# PicLEDThermometer.net
KiCad netlist of a schematic drawn in EAGLE
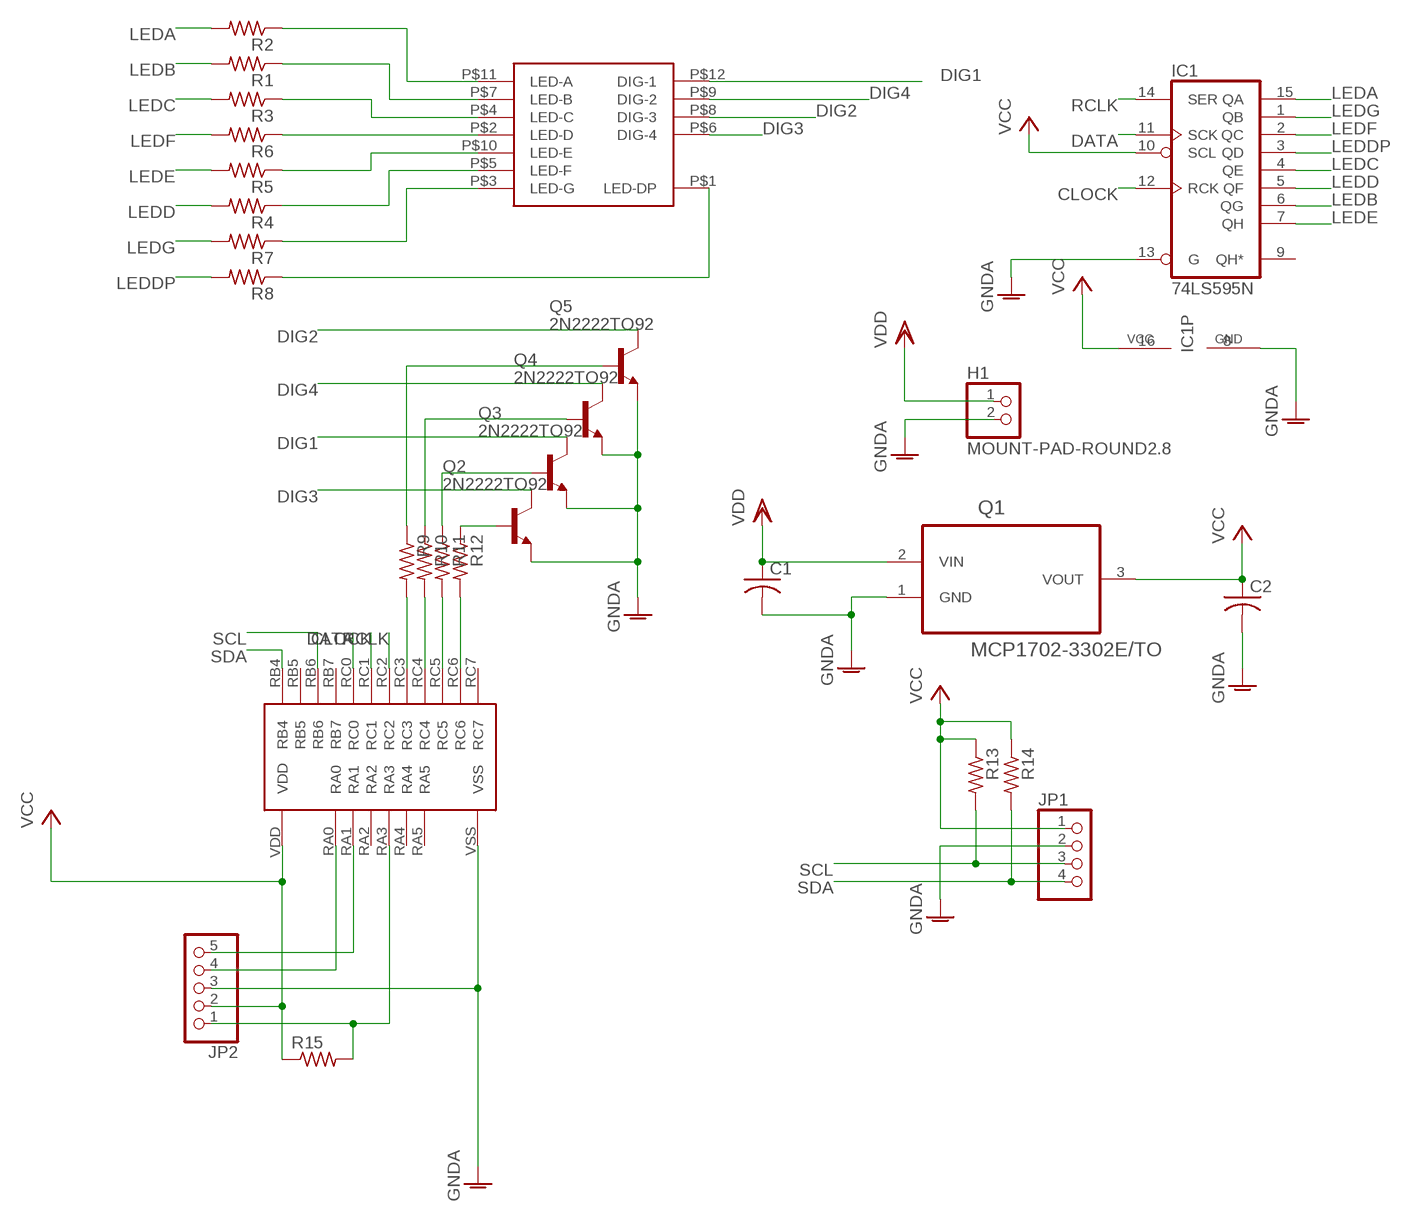
[diagram p0: schematic, sheet 1]

(export (version "E")
  (design (tool "Eeschema 10.0.6"))
  (components
    (comp (ref "C1")
      (value "C-US025-030X050")
      (footprint "eagle-import:C025-030X050")
      (libsource (lib "eagle-import") (part "C-US025-030X050"))
    )
    (comp (ref "C2")
      (value "C-US025-030X050")
      (footprint "eagle-import:C025-030X050")
      (libsource (lib "eagle-import") (part "C-US025-030X050"))
    )
    (comp (ref "H1")
      (value "MOUNT-PAD-ROUND2.8")
      (footprint "eagle-import:1X02")
      (libsource (lib "eagle-import") (part "PINHD-1X2"))
    )
    (comp (ref "IC1")
      (value "74LS595N")
      (footprint "eagle-import:DIL16")
      (libsource (lib "eagle-import") (part "74595NLS"))
    )
    (comp (ref "JP1")
      (value "PINHD-1X4")
      (footprint "eagle-import:1X04")
      (libsource (lib "eagle-import") (part "PINHD-1X4"))
    )
    (comp (ref "JP2")
      (value "PINHD-1X5")
      (footprint "eagle-import:1X05")
      (libsource (lib "eagle-import") (part "PINHD-1X5"))
    )
    (comp (ref "Q1")
      (value "MCP1702-3302E/TO")
      (footprint "eagle-import:TO127P254X533-3")
      (libsource (lib "eagle-import") (part "MCP1702-3302E/TO"))
    )
    (comp (ref "Q2")
      (value "2N2222TO92")
      (footprint "eagle-import:TO92-LINE")
      (libsource (lib "eagle-import") (part "2N2222TO92"))
    )
    (comp (ref "Q3")
      (value "2N2222TO92")
      (footprint "eagle-import:TO92-LINE")
      (libsource (lib "eagle-import") (part "2N2222TO92"))
    )
    (comp (ref "Q4")
      (value "2N2222TO92")
      (footprint "eagle-import:TO92-LINE")
      (libsource (lib "eagle-import") (part "2N2222TO92"))
    )
    (comp (ref "Q5")
      (value "2N2222TO92")
      (footprint "eagle-import:TO92-LINE")
      (libsource (lib "eagle-import") (part "2N2222TO92"))
    )
    (comp (ref "R1")
      (value "R-US_0207/10")
      (footprint "eagle-import:0207_10")
      (libsource (lib "eagle-import") (part "R-US_0207/10"))
    )
    (comp (ref "R2")
      (value "R-US_0207/10")
      (footprint "eagle-import:0207_10")
      (libsource (lib "eagle-import") (part "R-US_0207/10"))
    )
    (comp (ref "R3")
      (value "R-US_0207/10")
      (footprint "eagle-import:0207_10")
      (libsource (lib "eagle-import") (part "R-US_0207/10"))
    )
    (comp (ref "R4")
      (value "R-US_0207/10")
      (footprint "eagle-import:0207_10")
      (libsource (lib "eagle-import") (part "R-US_0207/10"))
    )
    (comp (ref "R5")
      (value "R-US_0207/10")
      (footprint "eagle-import:0207_10")
      (libsource (lib "eagle-import") (part "R-US_0207/10"))
    )
    (comp (ref "R6")
      (value "R-US_0207/10")
      (footprint "eagle-import:0207_10")
      (libsource (lib "eagle-import") (part "R-US_0207/10"))
    )
    (comp (ref "R7")
      (value "R-US_0207/10")
      (footprint "eagle-import:0207_10")
      (libsource (lib "eagle-import") (part "R-US_0207/10"))
    )
    (comp (ref "R8")
      (value "R-US_0207/10")
      (footprint "eagle-import:0207_10")
      (libsource (lib "eagle-import") (part "R-US_0207/10"))
    )
    (comp (ref "R9")
      (value "R-US_0207/10")
      (footprint "eagle-import:0207_10")
      (libsource (lib "eagle-import") (part "R-US_0207/10"))
    )
    (comp (ref "R10")
      (value "R-US_0207/10")
      (footprint "eagle-import:0207_10")
      (libsource (lib "eagle-import") (part "R-US_0207/10"))
    )
    (comp (ref "R11")
      (value "R-US_0207/10")
      (footprint "eagle-import:0207_10")
      (libsource (lib "eagle-import") (part "R-US_0207/10"))
    )
    (comp (ref "R12")
      (value "R-US_0207/10")
      (footprint "eagle-import:0207_10")
      (libsource (lib "eagle-import") (part "R-US_0207/10"))
    )
    (comp (ref "R13")
      (value "R-US_0207/10")
      (footprint "eagle-import:0207_10")
      (libsource (lib "eagle-import") (part "R-US_0207/10"))
    )
    (comp (ref "R14")
      (value "R-US_0207/10")
      (footprint "eagle-import:0207_10")
      (libsource (lib "eagle-import") (part "R-US_0207/10"))
    )
    (comp (ref "R15")
      (value "R-US_0207/10")
      (footprint "eagle-import:0207_10")
      (libsource (lib "eagle-import") (part "R-US_0207/10"))
    )
    (comp (ref "U$1")
      (value "FYQ-5641")
      (footprint "eagle-import:FYQ-5641")
      (libsource (lib "eagle-import") (part "FYQ-5641"))
    )
    (comp (ref "U$2")
      (value "PIC16F1707")
      (footprint "eagle-import:PIC16F1707")
      (libsource (lib "eagle-import") (part "PIC16F1707"))
    )
  )
  (nets
    (net (code "1") (name "/CLOCK") (class "Default")
      (node (ref "IC1") (pin "12") (pinfunction "RCK_12") (pintype "input"))
      (node (ref "U$2") (pin "RC1") (pinfunction "RC1_RC1") (pintype "bidirectional"))
    )
    (net (code "2") (name "/DATA") (class "Default")
      (node (ref "IC1") (pin "11") (pinfunction "SCK_11") (pintype "input"))
      (node (ref "U$2") (pin "RC0") (pinfunction "RC0_RC0") (pintype "bidirectional"))
    )
    (net (code "3") (name "/DIG1") (class "Default")
      (node (ref "Q3") (pin "COL") (pinfunction "C_COL") (pintype "passive"))
      (node (ref "U$1") (pin "P$12") (pinfunction "DIG-1_P$12") (pintype "bidirectional"))
    )
    (net (code "4") (name "/DIG2") (class "Default")
      (node (ref "Q5") (pin "COL") (pinfunction "C_COL") (pintype "passive"))
      (node (ref "U$1") (pin "P$8") (pinfunction "DIG-3_P$8") (pintype "bidirectional"))
    )
    (net (code "5") (name "/DIG3") (class "Default")
      (node (ref "Q2") (pin "COL") (pinfunction "C_COL") (pintype "passive"))
      (node (ref "U$1") (pin "P$6") (pinfunction "DIG-4_P$6") (pintype "bidirectional"))
    )
    (net (code "6") (name "/DIG4") (class "Default")
      (node (ref "Q4") (pin "COL") (pinfunction "C_COL") (pintype "passive"))
      (node (ref "U$1") (pin "P$9") (pinfunction "DIG-2_P$9") (pintype "bidirectional"))
    )
    (net (code "7") (name "/LEDA") (class "Default")
      (node (ref "IC1") (pin "15") (pinfunction "QA_15") (pintype "tri_state"))
      (node (ref "R2") (pin "2") (pinfunction "2_2") (pintype "passive"))
    )
    (net (code "8") (name "/LEDB") (class "Default")
      (node (ref "IC1") (pin "6") (pinfunction "QG_6") (pintype "tri_state"))
      (node (ref "R1") (pin "2") (pinfunction "2_2") (pintype "passive"))
    )
    (net (code "9") (name "/LEDC") (class "Default")
      (node (ref "IC1") (pin "4") (pinfunction "QE_4") (pintype "tri_state"))
      (node (ref "R3") (pin "2") (pinfunction "2_2") (pintype "passive"))
    )
    (net (code "10") (name "/LEDD") (class "Default")
      (node (ref "IC1") (pin "5") (pinfunction "QF_5") (pintype "tri_state"))
      (node (ref "R4") (pin "2") (pinfunction "2_2") (pintype "passive"))
    )
    (net (code "11") (name "/LEDDP") (class "Default")
      (node (ref "IC1") (pin "3") (pinfunction "QD_3") (pintype "tri_state"))
      (node (ref "R8") (pin "2") (pinfunction "2_2") (pintype "passive"))
    )
    (net (code "12") (name "/LEDE") (class "Default")
      (node (ref "IC1") (pin "7") (pinfunction "QH_7") (pintype "tri_state"))
      (node (ref "R5") (pin "2") (pinfunction "2_2") (pintype "passive"))
    )
    (net (code "13") (name "/LEDF") (class "Default")
      (node (ref "IC1") (pin "2") (pinfunction "QC_2") (pintype "tri_state"))
      (node (ref "R6") (pin "2") (pinfunction "2_2") (pintype "passive"))
    )
    (net (code "14") (name "/LEDG") (class "Default")
      (node (ref "IC1") (pin "1") (pinfunction "QB_1") (pintype "tri_state"))
      (node (ref "R7") (pin "2") (pinfunction "2_2") (pintype "passive"))
    )
    (net (code "15") (name "/RCLK") (class "Default")
      (node (ref "IC1") (pin "14") (pinfunction "SER_14") (pintype "input"))
      (node (ref "U$2") (pin "RC2") (pinfunction "RC2_RC2") (pintype "bidirectional"))
    )
    (net (code "16") (name "/SCL") (class "Default")
      (node (ref "JP1") (pin "3") (pinfunction "3_3") (pintype "passive"))
      (node (ref "R13") (pin "2") (pinfunction "2_2") (pintype "passive"))
      (node (ref "U$2") (pin "RB6") (pinfunction "RB6_RB6") (pintype "bidirectional"))
    )
    (net (code "17") (name "/SDA") (class "Default")
      (node (ref "JP1") (pin "4") (pinfunction "4_4") (pintype "passive"))
      (node (ref "R14") (pin "2") (pinfunction "2_2") (pintype "passive"))
      (node (ref "U$2") (pin "RB4") (pinfunction "RB4_RB4") (pintype "bidirectional"))
    )
    (net (code "18") (name "GNDA") (class "Default")
      (node (ref "C1") (pin "2") (pinfunction "2_2") (pintype "passive"))
      (node (ref "C2") (pin "2") (pinfunction "2_2") (pintype "passive"))
      (node (ref "H1") (pin "2") (pinfunction "2_2") (pintype "passive"))
      (node (ref "IC1") (pin "13") (pinfunction "G_13") (pintype "input"))
      (node (ref "IC1") (pin "8") (pinfunction "GND_8") (pintype "power_in"))
      (node (ref "JP1") (pin "2") (pinfunction "2_2") (pintype "passive"))
      (node (ref "JP2") (pin "3") (pinfunction "3_3") (pintype "passive"))
      (node (ref "Q1") (pin "1") (pinfunction "GND_1") (pintype "passive"))
      (node (ref "Q2") (pin "EMIT") (pinfunction "E_EMIT") (pintype "passive"))
      (node (ref "Q3") (pin "EMIT") (pinfunction "E_EMIT") (pintype "passive"))
      (node (ref "Q4") (pin "EMIT") (pinfunction "E_EMIT") (pintype "passive"))
      (node (ref "Q5") (pin "EMIT") (pinfunction "E_EMIT") (pintype "passive"))
      (node (ref "U$2") (pin "VSS") (pinfunction "VSS_VSS") (pintype "bidirectional"))
    )
    (net (code "19") (name "Net-(JP2-Pad1)") (class "Default")
      (node (ref "JP2") (pin "1") (pinfunction "1_1") (pintype "passive"))
      (node (ref "R15") (pin "2") (pinfunction "2_2") (pintype "passive"))
      (node (ref "U$2") (pin "RA3") (pinfunction "RA3_RA3") (pintype "bidirectional"))
    )
    (net (code "20") (name "Net-(JP2-Pad4)") (class "Default")
      (node (ref "JP2") (pin "4") (pinfunction "4_4") (pintype "passive"))
      (node (ref "U$2") (pin "RA0") (pinfunction "RA0_RA0") (pintype "bidirectional"))
    )
    (net (code "21") (name "Net-(JP2-Pad5)") (class "Default")
      (node (ref "JP2") (pin "5") (pinfunction "5_5") (pintype "passive"))
      (node (ref "U$2") (pin "RA1") (pinfunction "RA1_RA1") (pintype "bidirectional"))
    )
    (net (code "22") (name "Net-(Q2-B)") (class "Default")
      (node (ref "Q2") (pin "BASE") (pinfunction "B_BASE") (pintype "passive"))
      (node (ref "R12") (pin "1") (pinfunction "1_1") (pintype "passive"))
    )
    (net (code "23") (name "Net-(Q3-B)") (class "Default")
      (node (ref "Q3") (pin "BASE") (pinfunction "B_BASE") (pintype "passive"))
      (node (ref "R11") (pin "1") (pinfunction "1_1") (pintype "passive"))
    )
    (net (code "24") (name "Net-(Q4-B)") (class "Default")
      (node (ref "Q4") (pin "BASE") (pinfunction "B_BASE") (pintype "passive"))
      (node (ref "R10") (pin "1") (pinfunction "1_1") (pintype "passive"))
    )
    (net (code "25") (name "Net-(Q5-B)") (class "Default")
      (node (ref "Q5") (pin "BASE") (pinfunction "B_BASE") (pintype "passive"))
      (node (ref "R9") (pin "1") (pinfunction "1_1") (pintype "passive"))
    )
    (net (code "26") (name "Net-(R9-Pad2)") (class "Default")
      (node (ref "R9") (pin "2") (pinfunction "2_2") (pintype "passive"))
      (node (ref "U$2") (pin "RC3") (pinfunction "RC3_RC3") (pintype "bidirectional"))
    )
    (net (code "27") (name "Net-(R10-Pad2)") (class "Default")
      (node (ref "R10") (pin "2") (pinfunction "2_2") (pintype "passive"))
      (node (ref "U$2") (pin "RC4") (pinfunction "RC4_RC4") (pintype "bidirectional"))
    )
    (net (code "28") (name "Net-(R11-Pad2)") (class "Default")
      (node (ref "R11") (pin "2") (pinfunction "2_2") (pintype "passive"))
      (node (ref "U$2") (pin "RC5") (pinfunction "RC5_RC5") (pintype "bidirectional"))
    )
    (net (code "29") (name "Net-(R12-Pad2)") (class "Default")
      (node (ref "R12") (pin "2") (pinfunction "2_2") (pintype "passive"))
      (node (ref "U$2") (pin "RC6") (pinfunction "RC6_RC6") (pintype "bidirectional"))
    )
    (net (code "30") (name "Net-(U$1-LED-A)") (class "Default")
      (node (ref "R2") (pin "1") (pinfunction "1_1") (pintype "passive"))
      (node (ref "U$1") (pin "P$11") (pinfunction "LED-A_P$11") (pintype "bidirectional"))
    )
    (net (code "31") (name "Net-(U$1-LED-B)") (class "Default")
      (node (ref "R1") (pin "1") (pinfunction "1_1") (pintype "passive"))
      (node (ref "U$1") (pin "P$7") (pinfunction "LED-B_P$7") (pintype "bidirectional"))
    )
    (net (code "32") (name "Net-(U$1-LED-C)") (class "Default")
      (node (ref "R3") (pin "1") (pinfunction "1_1") (pintype "passive"))
      (node (ref "U$1") (pin "P$4") (pinfunction "LED-C_P$4") (pintype "bidirectional"))
    )
    (net (code "33") (name "Net-(U$1-LED-D)") (class "Default")
      (node (ref "R6") (pin "1") (pinfunction "1_1") (pintype "passive"))
      (node (ref "U$1") (pin "P$2") (pinfunction "LED-D_P$2") (pintype "bidirectional"))
    )
    (net (code "34") (name "Net-(U$1-LED-DP)") (class "Default")
      (node (ref "R8") (pin "1") (pinfunction "1_1") (pintype "passive"))
      (node (ref "U$1") (pin "P$1") (pinfunction "LED-DP_P$1") (pintype "bidirectional"))
    )
    (net (code "35") (name "Net-(U$1-LED-E)") (class "Default")
      (node (ref "R5") (pin "1") (pinfunction "1_1") (pintype "passive"))
      (node (ref "U$1") (pin "P$10") (pinfunction "LED-E_P$10") (pintype "bidirectional"))
    )
    (net (code "36") (name "Net-(U$1-LED-F)") (class "Default")
      (node (ref "R4") (pin "1") (pinfunction "1_1") (pintype "passive"))
      (node (ref "U$1") (pin "P$5") (pinfunction "LED-F_P$5") (pintype "bidirectional"))
    )
    (net (code "37") (name "Net-(U$1-LED-G)") (class "Default")
      (node (ref "R7") (pin "1") (pinfunction "1_1") (pintype "passive"))
      (node (ref "U$1") (pin "P$3") (pinfunction "LED-G_P$3") (pintype "bidirectional"))
    )
    (net (code "38") (name "VCC") (class "Default")
      (node (ref "C2") (pin "1") (pinfunction "1_1") (pintype "passive"))
      (node (ref "IC1") (pin "10") (pinfunction "SCL_10") (pintype "input"))
      (node (ref "IC1") (pin "16") (pinfunction "VCC_16") (pintype "power_in"))
      (node (ref "JP1") (pin "1") (pinfunction "1_1") (pintype "passive"))
      (node (ref "JP2") (pin "2") (pinfunction "2_2") (pintype "passive"))
      (node (ref "Q1") (pin "3") (pinfunction "VOUT_3") (pintype "output"))
      (node (ref "R13") (pin "1") (pinfunction "1_1") (pintype "passive"))
      (node (ref "R14") (pin "1") (pinfunction "1_1") (pintype "passive"))
      (node (ref "R15") (pin "1") (pinfunction "1_1") (pintype "passive"))
      (node (ref "U$2") (pin "VDD") (pinfunction "VDD_VDD") (pintype "bidirectional"))
    )
    (net (code "39") (name "VDD") (class "Default")
      (node (ref "C1") (pin "1") (pinfunction "1_1") (pintype "passive"))
      (node (ref "H1") (pin "1") (pinfunction "1_1") (pintype "passive"))
      (node (ref "Q1") (pin "2") (pinfunction "VIN_2") (pintype "input"))
    )
    (net (code "40") (name "unconnected-(IC1A-QH*-Pad9)") (class "Default")
      (node (ref "IC1") (pin "9") (pinfunction "QH*_9") (pintype "tri_state"))
    )
    (net (code "41") (name "unconnected-(U$2-PadRA2)") (class "Default")
      (node (ref "U$2") (pin "RA2") (pinfunction "RA2_RA2") (pintype "bidirectional"))
    )
    (net (code "42") (name "unconnected-(U$2-PadRA4)") (class "Default")
      (node (ref "U$2") (pin "RA4") (pinfunction "RA4_RA4") (pintype "bidirectional"))
    )
    (net (code "43") (name "unconnected-(U$2-PadRA5)") (class "Default")
      (node (ref "U$2") (pin "RA5") (pinfunction "RA5_RA5") (pintype "bidirectional"))
    )
    (net (code "44") (name "unconnected-(U$2-PadRB5)") (class "Default")
      (node (ref "U$2") (pin "RB5") (pinfunction "RB5_RB5") (pintype "bidirectional"))
    )
    (net (code "45") (name "unconnected-(U$2-PadRB7)") (class "Default")
      (node (ref "U$2") (pin "RB7") (pinfunction "RB7_RB7") (pintype "bidirectional"))
    )
    (net (code "46") (name "unconnected-(U$2-PadRC7)") (class "Default")
      (node (ref "U$2") (pin "RC7") (pinfunction "RC7_RC7") (pintype "bidirectional"))
    )
  )
)
